# VIDEO_IN_TVP5150.net
KiCad netlist of a schematic drawn in Altium Designer
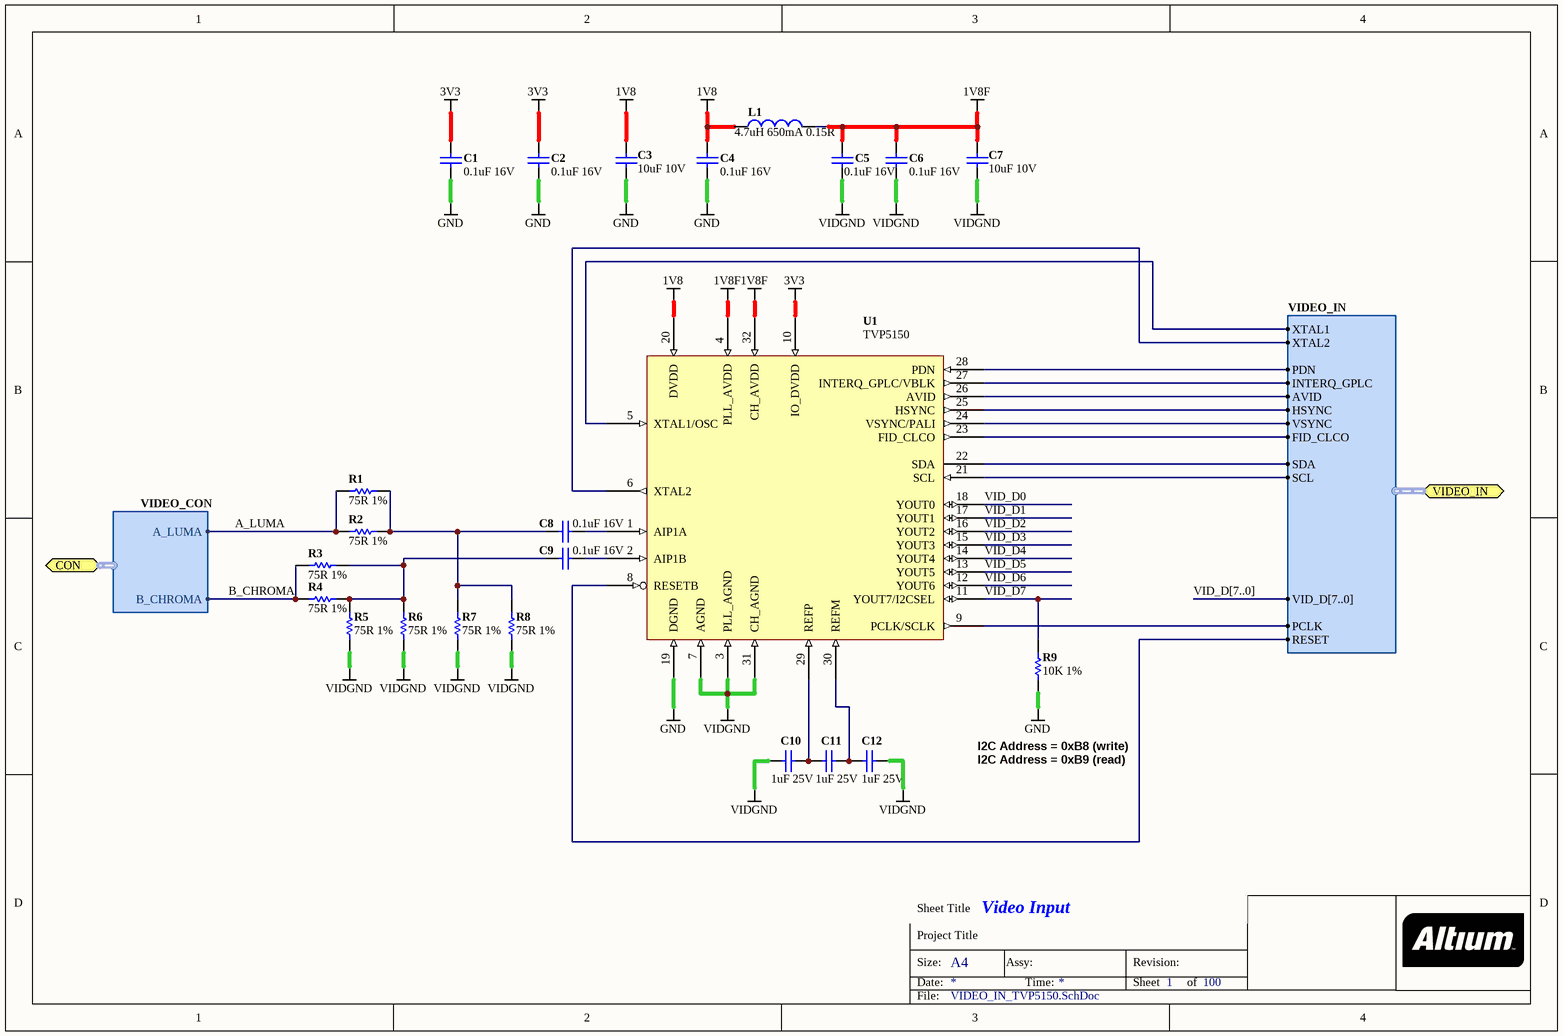
[diagram p0: VIDEO_IN_TVP5150.SchDoc]

(export (version "E")
  (design (tool "Eeschema 10.0.6"))
  (components
    (comp (ref "C1")
      (value "0.1uF 16V")
      (footprint "CAPC1005-STAR")
      (description "Capacitor, Ceramic, 0.1uF 10% 16V 0402 (1005) X7R")
      (fields (field (name "TOLERANCE") "10 %"))
      (libsource (lib "AltiumDesignLibrary") (part "CAP-NP"))
    )
    (comp (ref "C2")
      (value "0.1uF 16V")
      (footprint "CAPC1005-STAR")
      (description "Capacitor, Ceramic, 0.1uF 10% 16V 0402 (1005) X7R")
      (fields (field (name "TOLERANCE") "10 %"))
      (libsource (lib "AltiumDesignLibrary") (part "CAP-NP"))
    )
    (comp (ref "C3")
      (value "10uF 10V")
      (footprint "CAPC2012-STAR")
      (description "Capacitor, Ceramic, 10uF 10% 10V 0805 (2012) X5R")
      (fields (field (name "TOLERANCE") "10 %"))
      (libsource (lib "AltiumDesignLibrary") (part "CAP-NP"))
    )
    (comp (ref "C4")
      (value "0.1uF 16V")
      (footprint "CAPC1005-STAR")
      (description "Capacitor, Ceramic, 0.1uF 10% 16V 0402 (1005) X7R")
      (fields (field (name "TOLERANCE") "10 %"))
      (libsource (lib "AltiumDesignLibrary") (part "CAP-NP"))
    )
    (comp (ref "C5")
      (value "0.1uF 16V")
      (footprint "CAPC1005-STAR")
      (description "Capacitor, Ceramic, 0.1uF 10% 16V 0402 (1005) X7R")
      (fields (field (name "TOLERANCE") "10 %"))
      (libsource (lib "AltiumDesignLibrary") (part "CAP-NP"))
    )
    (comp (ref "C6")
      (value "0.1uF 16V")
      (footprint "CAPC1005-STAR")
      (description "Capacitor, Ceramic, 0.1uF 10% 16V 0402 (1005) X7R")
      (fields (field (name "TOLERANCE") "10 %"))
      (libsource (lib "AltiumDesignLibrary") (part "CAP-NP"))
    )
    (comp (ref "C7")
      (value "10uF 10V")
      (footprint "CAPC2012-STAR")
      (description "Capacitor, Ceramic, 10uF 10% 10V 0805 (2012) X5R")
      (fields (field (name "TOLERANCE") "10 %"))
      (libsource (lib "AltiumDesignLibrary") (part "CAP-NP"))
    )
    (comp (ref "C8")
      (value "0.1uF 16V")
      (footprint "CAPC1005-STAR")
      (description "Capacitor, Ceramic, 0.1uF 10% 16V 0402 (1005) X7R")
      (fields (field (name "TOLERANCE") "10 %"))
      (libsource (lib "AltiumDesignLibrary") (part "CAP-NP"))
    )
    (comp (ref "C9")
      (value "0.1uF 16V")
      (footprint "CAPC1005-STAR")
      (description "Capacitor, Ceramic, 0.1uF 10% 16V 0402 (1005) X7R")
      (fields (field (name "TOLERANCE") "10 %"))
      (libsource (lib "AltiumDesignLibrary") (part "CAP-NP"))
    )
    (comp (ref "C10")
      (value "1uF 25V")
      (footprint "CAPC3216-STAR")
      (description "Capacitor, Ceramic, 1uF 10% 25V 1206 (3216) X7R")
      (fields (field (name "TOLERANCE") "10 %"))
      (libsource (lib "AltiumDesignLibrary") (part "CAP-NP"))
    )
    (comp (ref "C11")
      (value "1uF 25V")
      (footprint "CAPC3216-STAR")
      (description "Capacitor, Ceramic, 1uF 10% 25V 1206 (3216) X7R")
      (fields (field (name "TOLERANCE") "10 %"))
      (libsource (lib "AltiumDesignLibrary") (part "CAP-NP"))
    )
    (comp (ref "C12")
      (value "1uF 25V")
      (footprint "CAPC3216-STAR")
      (description "Capacitor, Ceramic, 1uF 10% 25V 1206 (3216) X7R")
      (fields (field (name "TOLERANCE") "10 %"))
      (libsource (lib "AltiumDesignLibrary") (part "CAP-NP"))
    )
    (comp (ref "L1")
      (value "4.7uH 650mA 0.15R")
      (footprint "INDC3225")
      (description "Inductor, 4.7uH 650mA 0.15R 1210 (3225) LQH32CN4R7M11L")
      (libsource (lib "AltiumDesignLibrary") (part "IND"))
    )
    (comp (ref "R1")
      (value "75R 1%")
      (footprint "RESC1005-STAR")
      (description "Resistor, 75R 1% 0402")
      (fields (field (name "TOLERANCE") "1 %"))
      (libsource (lib "AltiumDesignLibrary") (part "RES"))
    )
    (comp (ref "R2")
      (value "75R 1%")
      (footprint "RESC1005-STAR")
      (description "Resistor, 75R 1% 0402")
      (fields (field (name "TOLERANCE") "1 %"))
      (libsource (lib "AltiumDesignLibrary") (part "RES"))
    )
    (comp (ref "R3")
      (value "75R 1%")
      (footprint "RESC1005-STAR")
      (description "Resistor, 75R 1% 0402")
      (fields (field (name "TOLERANCE") "1 %"))
      (libsource (lib "AltiumDesignLibrary") (part "RES"))
    )
    (comp (ref "R4")
      (value "75R 1%")
      (footprint "RESC1005-STAR")
      (description "Resistor, 75R 1% 0402")
      (fields (field (name "TOLERANCE") "1 %"))
      (libsource (lib "AltiumDesignLibrary") (part "RES"))
    )
    (comp (ref "R5")
      (value "75R 1%")
      (footprint "RESC1005-STAR")
      (description "Resistor, 75R 1% 0402")
      (fields (field (name "TOLERANCE") "1 %"))
      (libsource (lib "AltiumDesignLibrary") (part "RES"))
    )
    (comp (ref "R6")
      (value "75R 1%")
      (footprint "RESC1005-STAR")
      (description "Resistor, 75R 1% 0402")
      (fields (field (name "TOLERANCE") "1 %"))
      (libsource (lib "AltiumDesignLibrary") (part "RES"))
    )
    (comp (ref "R7")
      (value "75R 1%")
      (footprint "RESC1005-STAR")
      (description "Resistor, 75R 1% 0402")
      (fields (field (name "TOLERANCE") "1 %"))
      (libsource (lib "AltiumDesignLibrary") (part "RES"))
    )
    (comp (ref "R8")
      (value "75R 1%")
      (footprint "RESC1005-STAR")
      (description "Resistor, 75R 1% 0402")
      (fields (field (name "TOLERANCE") "1 %"))
      (libsource (lib "AltiumDesignLibrary") (part "RES"))
    )
    (comp (ref "R9")
      (value "10K 1%")
      (footprint "RESC1005-STAR")
      (description "Resistor, 10K 1% 0402 (1005)")
      (fields (field (name "TOLERANCE") "1 %"))
      (libsource (lib "AltiumDesignLibrary") (part "RES"))
    )
    (comp (ref "U1")
      (value "TVP5150")
      (footprint "TSQFP50P700X700-32")
      (description "TVP5150AM1PBS, Ultralow Power NTSC/PAL/SECAM Video Decoder With Robust Sync Detector")
      (libsource (lib "AltiumDesignLibrary") (part "TVP5150"))
    )
  )
  (nets
    (net (code "3") (name "/AVID") (class "Default")
      (node (ref "U1") (pin "26") (pinfunction "AVID_26") (pintype "output"))
    )
    (net (code "4") (name "/A_LUMA") (class "Default")
      (node (ref "R1") (pin "2") (pinfunction "2_2") (pintype "passive"))
      (node (ref "R2") (pin "2") (pinfunction "2_2") (pintype "passive"))
    )
    (net (code "5") (name "/B_CHROMA") (class "Default")
      (node (ref "R3") (pin "2") (pinfunction "2_2") (pintype "passive"))
      (node (ref "R4") (pin "1") (pinfunction "1_1") (pintype "passive"))
    )
    (net (code "6") (name "/FID_CLCO") (class "Default")
      (node (ref "U1") (pin "23") (pinfunction "FID_CLCO_23") (pintype "output"))
    )
    (net (code "7") (name "/HSYNC") (class "Default")
      (node (ref "U1") (pin "25") (pinfunction "HSYNC_25") (pintype "output"))
    )
    (net (code "8") (name "/INTERQ_GPLC") (class "Default")
      (node (ref "U1") (pin "27") (pinfunction "INTERQ_GPLC/VBLK_27") (pintype "output"))
    )
    (net (code "9") (name "/PCLK") (class "Default")
      (node (ref "U1") (pin "9") (pinfunction "PCLK/SCLK_9") (pintype "output"))
    )
    (net (code "10") (name "/PDN") (class "Default")
      (node (ref "U1") (pin "28") (pinfunction "PDN_28") (pintype "input"))
    )
    (net (code "11") (name "/RESET") (class "Default")
      (node (ref "U1") (pin "8") (pinfunction "RESETB_8") (pintype "input"))
    )
    (net (code "12") (name "/SCL") (class "Default")
      (node (ref "U1") (pin "21") (pinfunction "SCL_21") (pintype "input"))
    )
    (net (code "13") (name "/SDA") (class "Default")
      (node (ref "U1") (pin "22") (pinfunction "SDA_22") (pintype "open_collector"))
    )
    (net (code "14") (name "/VID_D0") (class "Default")
      (node (ref "U1") (pin "18") (pinfunction "YOUT0_18") (pintype "bidirectional"))
    )
    (net (code "15") (name "/VID_D1") (class "Default")
      (node (ref "U1") (pin "17") (pinfunction "YOUT1_17") (pintype "bidirectional"))
    )
    (net (code "16") (name "/VID_D2") (class "Default")
      (node (ref "U1") (pin "16") (pinfunction "YOUT2_16") (pintype "bidirectional"))
    )
    (net (code "17") (name "/VID_D3") (class "Default")
      (node (ref "U1") (pin "15") (pinfunction "YOUT3_15") (pintype "bidirectional"))
    )
    (net (code "18") (name "/VID_D4") (class "Default")
      (node (ref "U1") (pin "14") (pinfunction "YOUT4_14") (pintype "bidirectional"))
    )
    (net (code "19") (name "/VID_D5") (class "Default")
      (node (ref "U1") (pin "13") (pinfunction "YOUT5_13") (pintype "bidirectional"))
    )
    (net (code "20") (name "/VID_D6") (class "Default")
      (node (ref "U1") (pin "12") (pinfunction "YOUT6_12") (pintype "bidirectional"))
    )
    (net (code "21") (name "/VID_D7") (class "Default")
      (node (ref "R9") (pin "2") (pinfunction "2_2") (pintype "passive"))
      (node (ref "U1") (pin "11") (pinfunction "YOUT7/I2CSEL_11") (pintype "bidirectional"))
    )
    (net (code "23") (name "/VSYNC") (class "Default")
      (node (ref "U1") (pin "24") (pinfunction "VSYNC/PALI_24") (pintype "output"))
    )
    (net (code "24") (name "/XTAL1") (class "Default")
      (node (ref "U1") (pin "5") (pinfunction "XTAL1/OSC_5") (pintype "input"))
    )
    (net (code "25") (name "/XTAL2") (class "Default")
      (node (ref "U1") (pin "6") (pinfunction "XTAL2_6") (pintype "output"))
    )
    (net (code "28") (name "1V8") (class "Default")
      (node (ref "C3") (pin "1") (pinfunction "1_1") (pintype "passive"))
      (node (ref "C4") (pin "2") (pinfunction "2_2") (pintype "passive"))
      (node (ref "L1") (pin "2") (pinfunction "2_2") (pintype "passive"))
      (node (ref "U1") (pin "20") (pinfunction "DVDD_20") (pintype "input"))
    )
    (net (code "29") (name "1V8F") (class "Default")
      (node (ref "C5") (pin "2") (pinfunction "2_2") (pintype "passive"))
      (node (ref "C6") (pin "2") (pinfunction "2_2") (pintype "passive"))
      (node (ref "C7") (pin "1") (pinfunction "1_1") (pintype "passive"))
      (node (ref "L1") (pin "1") (pinfunction "1_1") (pintype "passive"))
      (node (ref "U1") (pin "32") (pinfunction "CH_AVDD_32") (pintype "input"))
      (node (ref "U1") (pin "4") (pinfunction "PLL_AVDD_4") (pintype "input"))
    )
    (net (code "30") (name "3V3") (class "Default")
      (node (ref "C1") (pin "2") (pinfunction "2_2") (pintype "passive"))
      (node (ref "C2") (pin "2") (pinfunction "2_2") (pintype "passive"))
      (node (ref "U1") (pin "10") (pinfunction "IO_DVDD_10") (pintype "input"))
    )
    (net (code "31") (name "GND") (class "Default")
      (node (ref "C1") (pin "1") (pinfunction "1_1") (pintype "passive"))
      (node (ref "C2") (pin "1") (pinfunction "1_1") (pintype "passive"))
      (node (ref "C3") (pin "2") (pinfunction "2_2") (pintype "passive"))
      (node (ref "C4") (pin "1") (pinfunction "1_1") (pintype "passive"))
      (node (ref "R9") (pin "1") (pinfunction "1_1") (pintype "passive"))
      (node (ref "U1") (pin "19") (pinfunction "DGND_19") (pintype "input"))
    )
    (net (code "32") (name "Net-(C8-Pad1)") (class "Default")
      (node (ref "C8") (pin "1") (pinfunction "1_1") (pintype "passive"))
      (node (ref "R1") (pin "1") (pinfunction "1_1") (pintype "passive"))
      (node (ref "R2") (pin "1") (pinfunction "1_1") (pintype "passive"))
      (node (ref "R7") (pin "2") (pinfunction "2_2") (pintype "passive"))
      (node (ref "R8") (pin "2") (pinfunction "2_2") (pintype "passive"))
    )
    (net (code "33") (name "Net-(C9-Pad1)") (class "Default")
      (node (ref "C9") (pin "1") (pinfunction "1_1") (pintype "passive"))
      (node (ref "R3") (pin "1") (pinfunction "1_1") (pintype "passive"))
      (node (ref "R4") (pin "2") (pinfunction "2_2") (pintype "passive"))
      (node (ref "R5") (pin "2") (pinfunction "2_2") (pintype "passive"))
      (node (ref "R6") (pin "2") (pinfunction "2_2") (pintype "passive"))
    )
    (net (code "34") (name "Net-(U1-AIP1A)") (class "Default")
      (node (ref "C8") (pin "2") (pinfunction "2_2") (pintype "passive"))
      (node (ref "U1") (pin "1") (pinfunction "AIP1A_1") (pintype "input"))
    )
    (net (code "35") (name "Net-(U1-AIP1B)") (class "Default")
      (node (ref "C9") (pin "2") (pinfunction "2_2") (pintype "passive"))
      (node (ref "U1") (pin "2") (pinfunction "AIP1B_2") (pintype "input"))
    )
    (net (code "36") (name "Net-(U1-REFM)") (class "Default")
      (node (ref "C11") (pin "1") (pinfunction "1_1") (pintype "passive"))
      (node (ref "C12") (pin "2") (pinfunction "2_2") (pintype "passive"))
      (node (ref "U1") (pin "30") (pinfunction "REFM_30") (pintype "input"))
    )
    (net (code "37") (name "Net-(U1-REFP)") (class "Default")
      (node (ref "C10") (pin "1") (pinfunction "1_1") (pintype "passive"))
      (node (ref "C11") (pin "2") (pinfunction "2_2") (pintype "passive"))
      (node (ref "U1") (pin "29") (pinfunction "REFP_29") (pintype "input"))
    )
    (net (code "38") (name "VIDGND") (class "Default")
      (node (ref "C10") (pin "2") (pinfunction "2_2") (pintype "passive"))
      (node (ref "C12") (pin "1") (pinfunction "1_1") (pintype "passive"))
      (node (ref "C5") (pin "1") (pinfunction "1_1") (pintype "passive"))
      (node (ref "C6") (pin "1") (pinfunction "1_1") (pintype "passive"))
      (node (ref "C7") (pin "2") (pinfunction "2_2") (pintype "passive"))
      (node (ref "R5") (pin "1") (pinfunction "1_1") (pintype "passive"))
      (node (ref "R6") (pin "1") (pinfunction "1_1") (pintype "passive"))
      (node (ref "R7") (pin "1") (pinfunction "1_1") (pintype "passive"))
      (node (ref "R8") (pin "1") (pinfunction "1_1") (pintype "passive"))
      (node (ref "U1") (pin "3") (pinfunction "PLL_AGND_3") (pintype "input"))
      (node (ref "U1") (pin "31") (pinfunction "CH_AGND_31") (pintype "input"))
      (node (ref "U1") (pin "7") (pinfunction "AGND_7") (pintype "input"))
    )
  )
)
